# PowerManager.net
KiCad netlist of a schematic drawn in Altium Designer
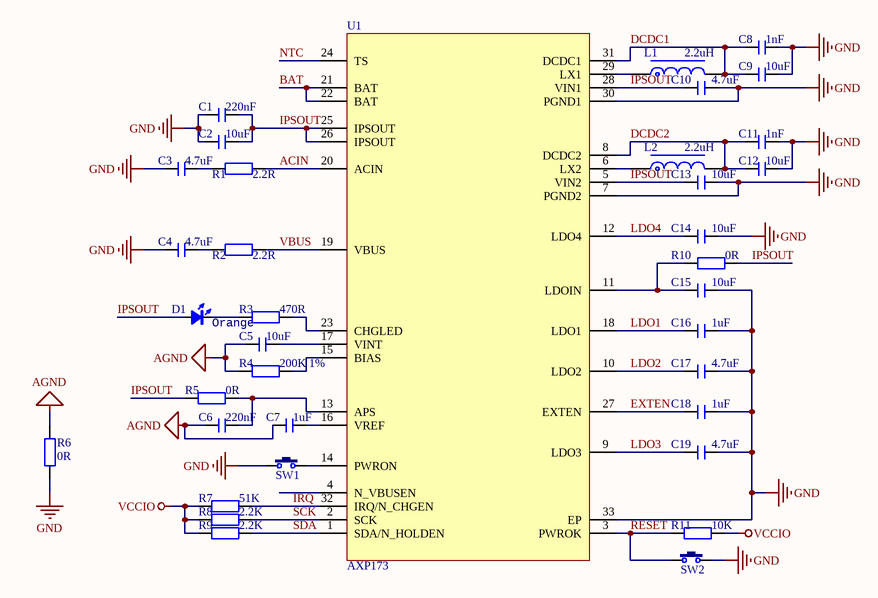
[diagram p0: PowerManager.SchDoc]

(export (version "E")
  (design (tool "Eeschema 10.0.6"))
  (components
    (comp (ref "C1")
      (value "220nF")
      (footprint "C 0603_L")
      (description "无极性贴片电容")
      (fields (field (name "版权归属") "源创客"))
      (libsource (lib "3.1   - 电阻-电容-电感") (part "C"))
    )
    (comp (ref "C2")
      (value "10uF")
      (footprint "C 0603_L")
      (description "无极性贴片电容")
      (fields (field (name "版权归属") "源创客"))
      (libsource (lib "3.1   - 电阻-电容-电感") (part "C"))
    )
    (comp (ref "C3")
      (value "4.7uF")
      (footprint "C 0603_L")
      (description "无极性贴片电容")
      (fields (field (name "版权归属") "源创客"))
      (libsource (lib "3.1   - 电阻-电容-电感") (part "C"))
    )
    (comp (ref "C4")
      (value "4.7uF")
      (footprint "C 0603_L")
      (description "无极性贴片电容")
      (fields (field (name "版权归属") "源创客"))
      (libsource (lib "3.1   - 电阻-电容-电感") (part "C"))
    )
    (comp (ref "C5")
      (value "10uF")
      (footprint "C 0603_L")
      (description "无极性贴片电容")
      (fields (field (name "版权归属") "源创客"))
      (libsource (lib "3.1   - 电阻-电容-电感") (part "C"))
    )
    (comp (ref "C6")
      (value "220nF")
      (footprint "C 0603_L")
      (description "无极性贴片电容")
      (fields (field (name "版权归属") "源创客"))
      (libsource (lib "3.1   - 电阻-电容-电感") (part "C"))
    )
    (comp (ref "C7")
      (value "1uF")
      (footprint "C 0603_L")
      (description "无极性贴片电容")
      (fields (field (name "版权归属") "源创客"))
      (libsource (lib "3.1   - 电阻-电容-电感") (part "C"))
    )
    (comp (ref "C8")
      (value "1nF")
      (footprint "C 0603_L")
      (description "无极性贴片电容")
      (fields (field (name "版权归属") "源创客"))
      (libsource (lib "3.1   - 电阻-电容-电感") (part "C"))
    )
    (comp (ref "C9")
      (value "10uF")
      (footprint "C 0805_L")
      (description "无极性贴片电容")
      (fields (field (name "版权归属") "源创客"))
      (libsource (lib "3.1   - 电阻-电容-电感") (part "C"))
    )
    (comp (ref "C10")
      (value "4.7uF")
      (footprint "C 0603_L")
      (description "无极性贴片电容")
      (fields (field (name "版权归属") "源创客"))
      (libsource (lib "3.1   - 电阻-电容-电感") (part "C"))
    )
    (comp (ref "C11")
      (value "1nF")
      (footprint "C 0603_L")
      (description "无极性贴片电容")
      (fields (field (name "版权归属") "源创客"))
      (libsource (lib "3.1   - 电阻-电容-电感") (part "C"))
    )
    (comp (ref "C12")
      (value "10uF")
      (footprint "C 0805_L")
      (description "无极性贴片电容")
      (fields (field (name "版权归属") "源创客"))
      (libsource (lib "3.1   - 电阻-电容-电感") (part "C"))
    )
    (comp (ref "C13")
      (value "10uF")
      (footprint "C 0603_L")
      (description "无极性贴片电容")
      (fields (field (name "版权归属") "源创客"))
      (libsource (lib "3.1   - 电阻-电容-电感") (part "C"))
    )
    (comp (ref "C14")
      (value "10uF")
      (footprint "C 0603_L")
      (description "无极性贴片电容")
      (fields (field (name "版权归属") "源创客"))
      (libsource (lib "3.1   - 电阻-电容-电感") (part "C"))
    )
    (comp (ref "C15")
      (value "10uF")
      (footprint "C 0603_L")
      (description "无极性贴片电容")
      (fields (field (name "版权归属") "源创客"))
      (libsource (lib "3.1   - 电阻-电容-电感") (part "C"))
    )
    (comp (ref "C16")
      (value "1uF")
      (footprint "C 0603_L")
      (description "无极性贴片电容")
      (fields (field (name "版权归属") "源创客"))
      (libsource (lib "3.1   - 电阻-电容-电感") (part "C"))
    )
    (comp (ref "C17")
      (value "4.7uF")
      (footprint "C 0603_L")
      (description "无极性贴片电容")
      (fields (field (name "版权归属") "源创客"))
      (libsource (lib "3.1   - 电阻-电容-电感") (part "C"))
    )
    (comp (ref "C18")
      (value "1uF")
      (footprint "C 0603_L")
      (description "无极性贴片电容")
      (fields (field (name "版权归属") "源创客"))
      (libsource (lib "3.1   - 电阻-电容-电感") (part "C"))
    )
    (comp (ref "C19")
      (value "4.7uF")
      (footprint "C 0603_L")
      (description "无极性贴片电容")
      (fields (field (name "版权归属") "源创客"))
      (libsource (lib "3.1   - 电阻-电容-电感") (part "C"))
    )
    (comp (ref "D1")
      (value "Orange")
      (footprint "PCB_ActiveLED:LED_0603_ORANGE")
      (description "LED")
      (libsource (lib "SCH_Active") (part "LED_0603"))
    )
    (comp (ref "L1")
      (value "2.2uH")
      (footprint "NR3015")
      (description "NR磁胶电感")
      (fields (field (name "版权归属") "源创客"))
      (libsource (lib "3.1   - 电阻-电容-电感") (part "L-NR"))
    )
    (comp (ref "L2")
      (value "2.2uH")
      (footprint "NR3015")
      (description "NR磁胶电感")
      (fields (field (name "版权归属") "源创客"))
      (libsource (lib "3.1   - 电阻-电容-电感") (part "L-NR"))
    )
    (comp (ref "R1")
      (value "2.2R")
      (footprint "R 0603_L")
      (description "贴片电阻")
      (fields (field (name "版权归属") "源创客"))
      (libsource (lib "3.1   - 电阻-电容-电感") (part "R"))
    )
    (comp (ref "R2")
      (value "2.2R")
      (footprint "R 0603_L")
      (description "贴片电阻")
      (fields (field (name "版权归属") "源创客"))
      (libsource (lib "3.1   - 电阻-电容-电感") (part "R"))
    )
    (comp (ref "R3")
      (value "470R")
      (footprint "R 0603_L")
      (description "贴片电阻")
      (fields (field (name "版权归属") "源创客"))
      (libsource (lib "3.1   - 电阻-电容-电感") (part "R"))
    )
    (comp (ref "R4")
      (value "200K 1%")
      (footprint "R 0603_L")
      (description "贴片电阻")
      (fields (field (name "版权归属") "源创客"))
      (libsource (lib "3.1   - 电阻-电容-电感") (part "R"))
    )
    (comp (ref "R5")
      (value "0R")
      (footprint "R 0603_L")
      (description "贴片电阻")
      (fields (field (name "版权归属") "源创客"))
      (libsource (lib "3.1   - 电阻-电容-电感") (part "R"))
    )
    (comp (ref "R6")
      (value "0R")
      (footprint "R 0603_L")
      (description "贴片电阻")
      (fields (field (name "版权归属") "源创客"))
      (libsource (lib "3.1   - 电阻-电容-电感") (part "R"))
    )
    (comp (ref "R7")
      (value "51K")
      (footprint "R 0603_L")
      (description "贴片电阻")
      (fields (field (name "版权归属") "源创客"))
      (libsource (lib "3.1   - 电阻-电容-电感") (part "R"))
    )
    (comp (ref "R8")
      (value "2.2K")
      (footprint "R 0603_L")
      (description "贴片电阻")
      (fields (field (name "版权归属") "源创客"))
      (libsource (lib "3.1   - 电阻-电容-电感") (part "R"))
    )
    (comp (ref "R9")
      (value "2.2K")
      (footprint "R 0603_L")
      (description "贴片电阻")
      (fields (field (name "版权归属") "源创客"))
      (libsource (lib "3.1   - 电阻-电容-电感") (part "R"))
    )
    (comp (ref "R10")
      (value "0R")
      (footprint "R 0603_L")
      (description "贴片电阻")
      (fields (field (name "版权归属") "源创客"))
      (libsource (lib "3.1   - 电阻-电容-电感") (part "R"))
    )
    (comp (ref "R11")
      (value "10K")
      (footprint "R 0603_L")
      (description "贴片电阻")
      (fields (field (name "版权归属") "源创客"))
      (libsource (lib "3.1   - 电阻-电容-电感") (part "R"))
    )
    (comp (ref "SW1")
      (value "3x6x5")
      (footprint "TSW 3*6*4.3-S-W")
      (description "3x6轻触开关")
      (fields (field (name "版权归属") "源创客"))
      (libsource (lib "5.1   - 按键-开关") (part "TSW 3x6"))
    )
    (comp (ref "SW2")
      (value "3x6x5")
      (footprint "TSW 3*6*4.3-S-W")
      (description "3x6轻触开关")
      (fields (field (name "版权归属") "源创客"))
      (libsource (lib "5.1   - 按键-开关") (part "TSW 3x6"))
    )
    (comp (ref "U1") (value "AXP173") (footprint "QFN32 5x5_L") (libsource (lib "LuLib") (part "AXP173")))
  )
  (nets
    (net (code "1") (name "/ACIN") (class "Default")
      (node (ref "R1") (pin "2") (pinfunction "2_2") (pintype "passive"))
      (node (ref "U1") (pin "20") (pinfunction "ACIN_20") (pintype "passive"))
    )
    (net (code "2") (name "/BAT") (class "Default")
      (node (ref "U1") (pin "21") (pinfunction "BAT_21") (pintype "passive"))
      (node (ref "U1") (pin "22") (pinfunction "BAT_22") (pintype "passive"))
    )
    (net (code "3") (name "/DCDC1") (class "Default")
      (node (ref "C8") (pin "2") (pinfunction "2_2") (pintype "passive"))
      (node (ref "C9") (pin "1") (pinfunction "1_1") (pintype "passive"))
      (node (ref "L1") (pin "2") (pinfunction "2_2") (pintype "passive"))
      (node (ref "U1") (pin "31") (pinfunction "DCDC1_31") (pintype "passive"))
    )
    (net (code "4") (name "/DCDC2") (class "Default")
      (node (ref "C11") (pin "2") (pinfunction "2_2") (pintype "passive"))
      (node (ref "C12") (pin "1") (pinfunction "1_1") (pintype "passive"))
      (node (ref "L2") (pin "2") (pinfunction "2_2") (pintype "passive"))
      (node (ref "U1") (pin "8") (pinfunction "DCDC2_8") (pintype "passive"))
    )
    (net (code "5") (name "/EXTEN") (class "Default")
      (node (ref "C18") (pin "1") (pinfunction "1_1") (pintype "passive"))
      (node (ref "U1") (pin "27") (pinfunction "EXTEN_27") (pintype "passive"))
    )
    (net (code "6") (name "/IPSOUT") (class "Default")
      (node (ref "C1") (pin "2") (pinfunction "2_2") (pintype "passive"))
      (node (ref "C10") (pin "1") (pinfunction "1_1") (pintype "passive"))
      (node (ref "C13") (pin "1") (pinfunction "1_1") (pintype "passive"))
      (node (ref "C2") (pin "2") (pinfunction "2_2") (pintype "passive"))
      (node (ref "D1") (pin "1") (pinfunction "A_1") (pintype "passive"))
      (node (ref "R10") (pin "1") (pinfunction "1_1") (pintype "passive"))
      (node (ref "R5") (pin "2") (pinfunction "2_2") (pintype "passive"))
      (node (ref "U1") (pin "25") (pinfunction "IPSOUT_25") (pintype "passive"))
      (node (ref "U1") (pin "26") (pinfunction "IPSOUT_26") (pintype "passive"))
      (node (ref "U1") (pin "28") (pinfunction "VIN1_28") (pintype "passive"))
      (node (ref "U1") (pin "5") (pinfunction "VIN2_5") (pintype "passive"))
    )
    (net (code "7") (name "/IRQ") (class "Default")
      (node (ref "R7") (pin "1") (pinfunction "1_1") (pintype "passive"))
      (node (ref "U1") (pin "32") (pinfunction "IRQ/N_CHGEN_32") (pintype "passive"))
    )
    (net (code "8") (name "/LDO1") (class "Default")
      (node (ref "C16") (pin "1") (pinfunction "1_1") (pintype "passive"))
      (node (ref "U1") (pin "18") (pinfunction "LDO1_18") (pintype "passive"))
    )
    (net (code "9") (name "/LDO2") (class "Default")
      (node (ref "C17") (pin "1") (pinfunction "1_1") (pintype "passive"))
      (node (ref "U1") (pin "10") (pinfunction "LDO2_10") (pintype "passive"))
    )
    (net (code "10") (name "/LDO3") (class "Default")
      (node (ref "C19") (pin "1") (pinfunction "1_1") (pintype "passive"))
      (node (ref "U1") (pin "9") (pinfunction "LDO3_9") (pintype "passive"))
    )
    (net (code "11") (name "/LDO4") (class "Default")
      (node (ref "C14") (pin "1") (pinfunction "1_1") (pintype "passive"))
      (node (ref "U1") (pin "12") (pinfunction "LDO4_12") (pintype "passive"))
    )
    (net (code "12") (name "/NTC") (class "Default")
      (node (ref "U1") (pin "24") (pinfunction "TS_24") (pintype "passive"))
    )
    (net (code "13") (name "/RESET") (class "Default")
      (node (ref "R11") (pin "2") (pinfunction "2_2") (pintype "passive"))
      (node (ref "SW2") (pin "1") (pinfunction "1_1") (pintype "passive"))
      (node (ref "U1") (pin "3") (pinfunction "PWROK_3") (pintype "passive"))
    )
    (net (code "14") (name "/SCK") (class "Default")
      (node (ref "R8") (pin "1") (pinfunction "1_1") (pintype "passive"))
      (node (ref "U1") (pin "2") (pinfunction "SCK_2") (pintype "passive"))
    )
    (net (code "15") (name "/SDA") (class "Default")
      (node (ref "R9") (pin "1") (pinfunction "1_1") (pintype "passive"))
      (node (ref "U1") (pin "1") (pinfunction "SDA/N_HOLDEN_1") (pintype "passive"))
    )
    (net (code "16") (name "/VBUS") (class "Default")
      (node (ref "R2") (pin "2") (pinfunction "2_2") (pintype "passive"))
      (node (ref "U1") (pin "19") (pinfunction "VBUS_19") (pintype "passive"))
    )
    (net (code "17") (name "AGND") (class "Default")
      (node (ref "C5") (pin "2") (pinfunction "2_2") (pintype "passive"))
      (node (ref "C6") (pin "2") (pinfunction "2_2") (pintype "passive"))
      (node (ref "C7") (pin "2") (pinfunction "2_2") (pintype "passive"))
      (node (ref "R4") (pin "2") (pinfunction "2_2") (pintype "passive"))
      (node (ref "R6") (pin "2") (pinfunction "2_2") (pintype "passive"))
    )
    (net (code "18") (name "GND") (class "Default")
      (node (ref "C1") (pin "1") (pinfunction "1_1") (pintype "passive"))
      (node (ref "C10") (pin "2") (pinfunction "2_2") (pintype "passive"))
      (node (ref "C11") (pin "1") (pinfunction "1_1") (pintype "passive"))
      (node (ref "C12") (pin "2") (pinfunction "2_2") (pintype "passive"))
      (node (ref "C13") (pin "2") (pinfunction "2_2") (pintype "passive"))
      (node (ref "C14") (pin "2") (pinfunction "2_2") (pintype "passive"))
      (node (ref "C15") (pin "2") (pinfunction "2_2") (pintype "passive"))
      (node (ref "C16") (pin "2") (pinfunction "2_2") (pintype "passive"))
      (node (ref "C17") (pin "2") (pinfunction "2_2") (pintype "passive"))
      (node (ref "C18") (pin "2") (pinfunction "2_2") (pintype "passive"))
      (node (ref "C19") (pin "2") (pinfunction "2_2") (pintype "passive"))
      (node (ref "C2") (pin "1") (pinfunction "1_1") (pintype "passive"))
      (node (ref "C3") (pin "1") (pinfunction "1_1") (pintype "passive"))
      (node (ref "C4") (pin "1") (pinfunction "1_1") (pintype "passive"))
      (node (ref "C8") (pin "1") (pinfunction "1_1") (pintype "passive"))
      (node (ref "C9") (pin "2") (pinfunction "2_2") (pintype "passive"))
      (node (ref "R6") (pin "1") (pinfunction "1_1") (pintype "passive"))
      (node (ref "SW1") (pin "1") (pinfunction "1_1") (pintype "passive"))
      (node (ref "SW2") (pin "2") (pinfunction "2_2") (pintype "passive"))
      (node (ref "U1") (pin "30") (pinfunction "PGND1_30") (pintype "passive"))
      (node (ref "U1") (pin "33") (pinfunction "EP_33") (pintype "passive"))
      (node (ref "U1") (pin "7") (pinfunction "PGND2_7") (pintype "passive"))
    )
    (net (code "19") (name "Net-(C3-Pad2)") (class "Default")
      (node (ref "C3") (pin "2") (pinfunction "2_2") (pintype "passive"))
      (node (ref "R1") (pin "1") (pinfunction "1_1") (pintype "passive"))
    )
    (net (code "20") (name "Net-(C4-Pad2)") (class "Default")
      (node (ref "C4") (pin "2") (pinfunction "2_2") (pintype "passive"))
      (node (ref "R2") (pin "1") (pinfunction "1_1") (pintype "passive"))
    )
    (net (code "21") (name "Net-(D1-K)") (class "Default")
      (node (ref "D1") (pin "2") (pinfunction "K_2") (pintype "passive"))
      (node (ref "R3") (pin "1") (pinfunction "1_1") (pintype "passive"))
    )
    (net (code "22") (name "Net-(U1-APS)") (class "Default")
      (node (ref "C6") (pin "1") (pinfunction "1_1") (pintype "passive"))
      (node (ref "R5") (pin "1") (pinfunction "1_1") (pintype "passive"))
      (node (ref "U1") (pin "13") (pinfunction "APS_13") (pintype "passive"))
    )
    (net (code "23") (name "Net-(U1-BIAS)") (class "Default")
      (node (ref "R4") (pin "1") (pinfunction "1_1") (pintype "passive"))
      (node (ref "U1") (pin "15") (pinfunction "BIAS_15") (pintype "passive"))
    )
    (net (code "24") (name "Net-(U1-CHGLED)") (class "Default")
      (node (ref "R3") (pin "2") (pinfunction "2_2") (pintype "passive"))
      (node (ref "U1") (pin "23") (pinfunction "CHGLED_23") (pintype "passive"))
    )
    (net (code "25") (name "Net-(U1-LDOIN)") (class "Default")
      (node (ref "C15") (pin "1") (pinfunction "1_1") (pintype "passive"))
      (node (ref "R10") (pin "2") (pinfunction "2_2") (pintype "passive"))
      (node (ref "U1") (pin "11") (pinfunction "LDOIN_11") (pintype "passive"))
    )
    (net (code "26") (name "Net-(U1-LX1)") (class "Default")
      (node (ref "L1") (pin "1") (pinfunction "1_1") (pintype "passive"))
      (node (ref "U1") (pin "29") (pinfunction "LX1_29") (pintype "passive"))
    )
    (net (code "27") (name "Net-(U1-LX2)") (class "Default")
      (node (ref "L2") (pin "1") (pinfunction "1_1") (pintype "passive"))
      (node (ref "U1") (pin "6") (pinfunction "LX2_6") (pintype "passive"))
    )
    (net (code "28") (name "Net-(U1-PWRON)") (class "Default")
      (node (ref "SW1") (pin "2") (pinfunction "2_2") (pintype "passive"))
      (node (ref "U1") (pin "14") (pinfunction "PWRON_14") (pintype "passive"))
    )
    (net (code "29") (name "Net-(U1-VINT)") (class "Default")
      (node (ref "C5") (pin "1") (pinfunction "1_1") (pintype "passive"))
      (node (ref "U1") (pin "17") (pinfunction "VINT_17") (pintype "passive"))
    )
    (net (code "30") (name "Net-(U1-VREF)") (class "Default")
      (node (ref "C7") (pin "1") (pinfunction "1_1") (pintype "passive"))
      (node (ref "U1") (pin "16") (pinfunction "VREF_16") (pintype "passive"))
    )
    (net (code "31") (name "VCCIO") (class "Default")
      (node (ref "R11") (pin "1") (pinfunction "1_1") (pintype "passive"))
      (node (ref "R7") (pin "2") (pinfunction "2_2") (pintype "passive"))
      (node (ref "R8") (pin "2") (pinfunction "2_2") (pintype "passive"))
      (node (ref "R9") (pin "2") (pinfunction "2_2") (pintype "passive"))
    )
    (net (code "32") (name "unconnected-(U1-N_VBUSEN-Pad4)") (class "Default")
      (node (ref "U1") (pin "4") (pinfunction "N_VBUSEN_4") (pintype "passive"))
    )
  )
)
